# Power.net
KiCad netlist of a schematic drawn in Altium Designer
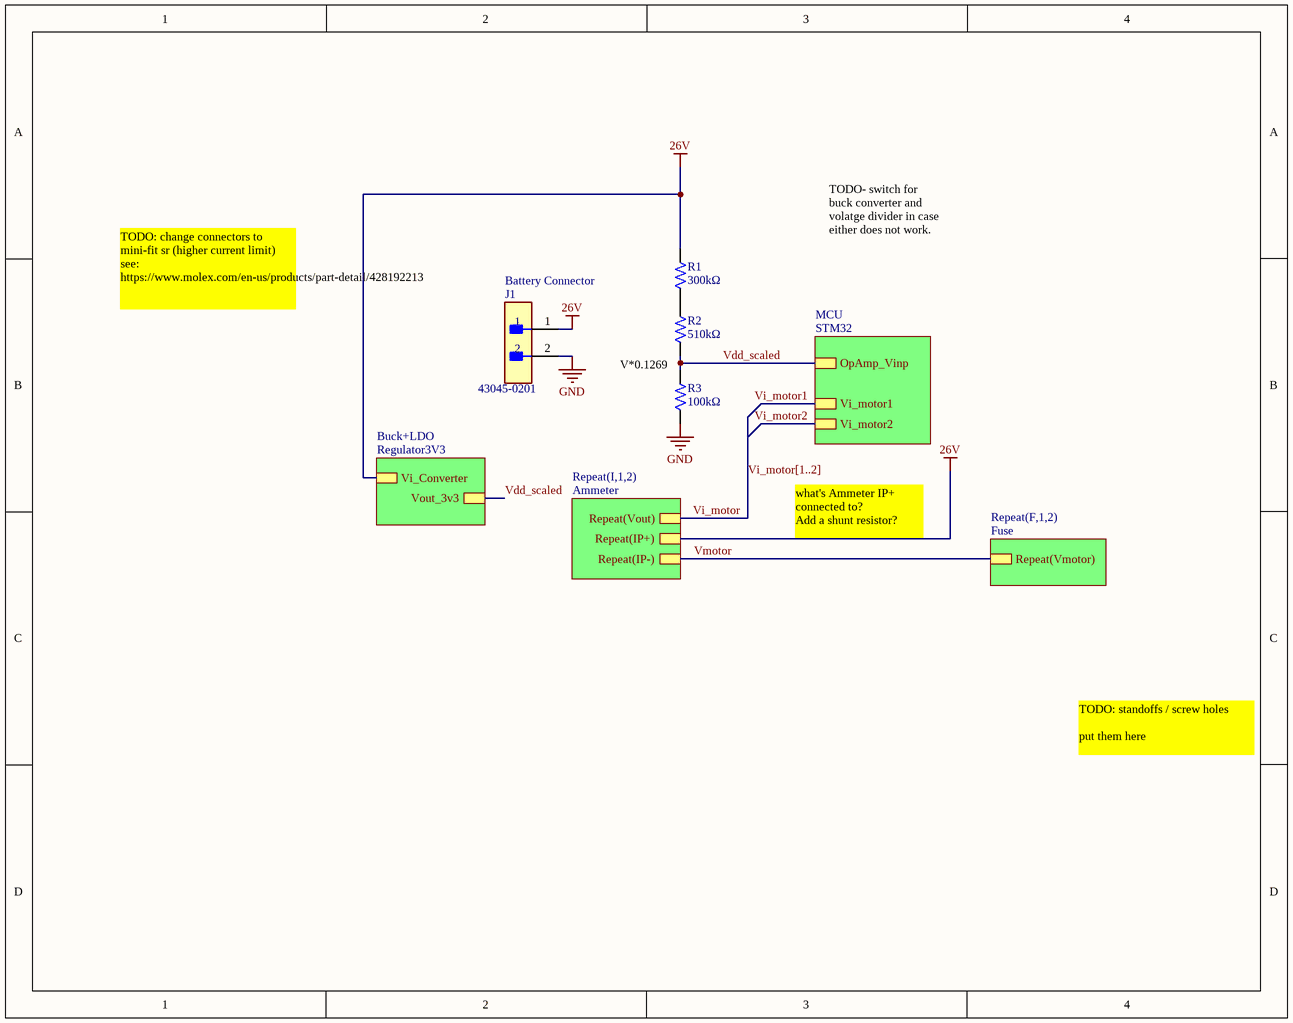
[diagram p0: Power.SchDoc]

(export (version "E")
  (design (tool "Eeschema 10.0.6"))
  (components
    (comp (ref "J1")
      (value "43045-0201")
      (footprint "FP-43045-0201-MFG")
      (description "CONN HEADER R/A 2POS")
      (libsource (lib "Altium Content Vault") (part "3bc925449376181038e59eaffc5286c"))
    )
    (comp (ref "R1")
      (value "0603WAF3003T5E")
      (footprint "RES-0603")
      (description "Resistor, 300kΩ, ±1%, 100mW, 75V, ±100ppm/℃, -55℃~+155℃, SMD 0603")
      (fields
        (field (name "MANUFACTURER") "Uniroyal")
        (field (name "JLCPCB PART NUMBER") "C23024")
        (field (name "RESISTANCE") "300kΩ")
      )
      (libsource (lib "jlcpcb_2024_10_resistors_basic") (part "0603WAF3003T5E"))
    )
    (comp (ref "R2")
      (value "0603WAF5103T5E")
      (footprint "RES-0603")
      (description "Resistor, 510kΩ, ±1%, 100mW, 75V, ±100ppm/℃, -55℃~+155℃, SMD 0603")
      (fields
        (field (name "MANUFACTURER") "Uniroyal")
        (field (name "JLCPCB PART NUMBER") "C23192")
        (field (name "RESISTANCE") "510kΩ")
      )
      (libsource (lib "jlcpcb_2024_10_resistors_basic") (part "0603WAF5103T5E"))
    )
    (comp (ref "R3")
      (value "0402WGF1003TCE")
      (footprint "RES-0402")
      (description "Resistor, 100kΩ, ±1%, 62.5mW, 50V, ±100ppm/℃, -55℃~+155℃, SMD 0402")
      (fields
        (field (name "MANUFACTURER") "Uniroyal")
        (field (name "JLCPCB PART NUMBER") "C25741")
        (field (name "RESISTANCE") "100kΩ")
      )
      (libsource (lib "jlcpcb_2024_10_resistors_basic") (part "0402WGF1003TCE"))
    )
  )
  (nets
    (net (code "2") (name "/Vdd_scaled") (class "Default")
      (node (ref "R2") (pin "1") (pinfunction "1_1") (pintype "passive"))
      (node (ref "R3") (pin "2") (pinfunction "2_2") (pintype "passive"))
    )
    (net (code "8") (name "26V") (class "Default")
      (node (ref "J1") (pin "1") (pinfunction "1_1") (pintype "passive"))
      (node (ref "R1") (pin "2") (pinfunction "2_2") (pintype "passive"))
    )
    (net (code "9") (name "GND") (class "Default")
      (node (ref "J1") (pin "2") (pinfunction "2_2") (pintype "passive"))
      (node (ref "R3") (pin "1") (pinfunction "1_1") (pintype "passive"))
    )
    (net (code "10") (name "Net-(R1-Pad1)") (class "Default")
      (node (ref "R1") (pin "1") (pinfunction "1_1") (pintype "passive"))
      (node (ref "R2") (pin "2") (pinfunction "2_2") (pintype "passive"))
    )
  )
)
